# esp32_uart_co2_sensor.net
KiCad netlist of a schematic drawn in EAGLE
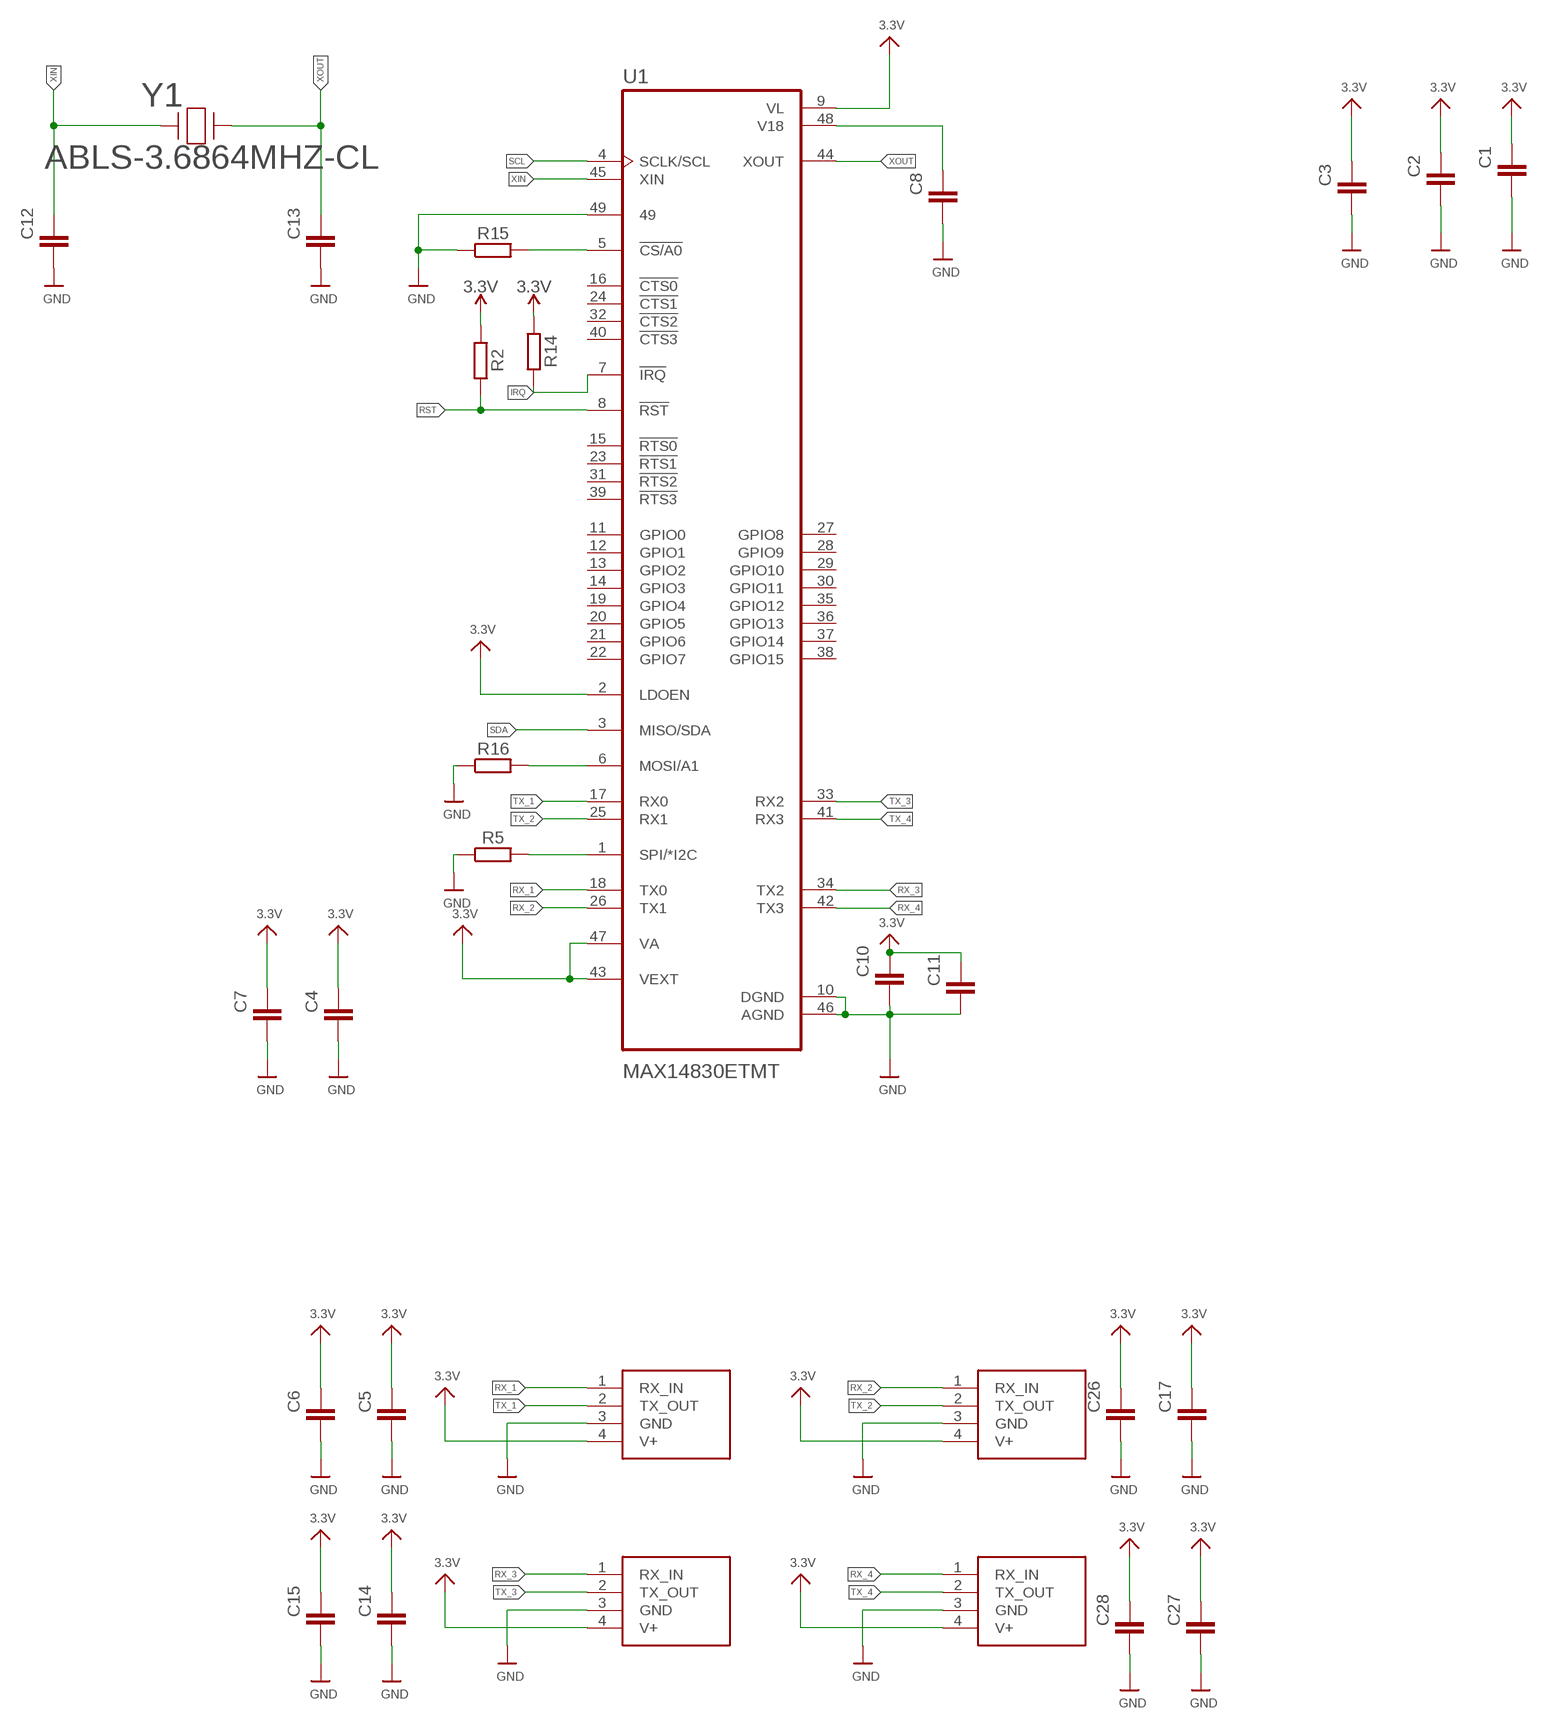
[diagram p0: schematic, sheet 1, part 1 of 2]
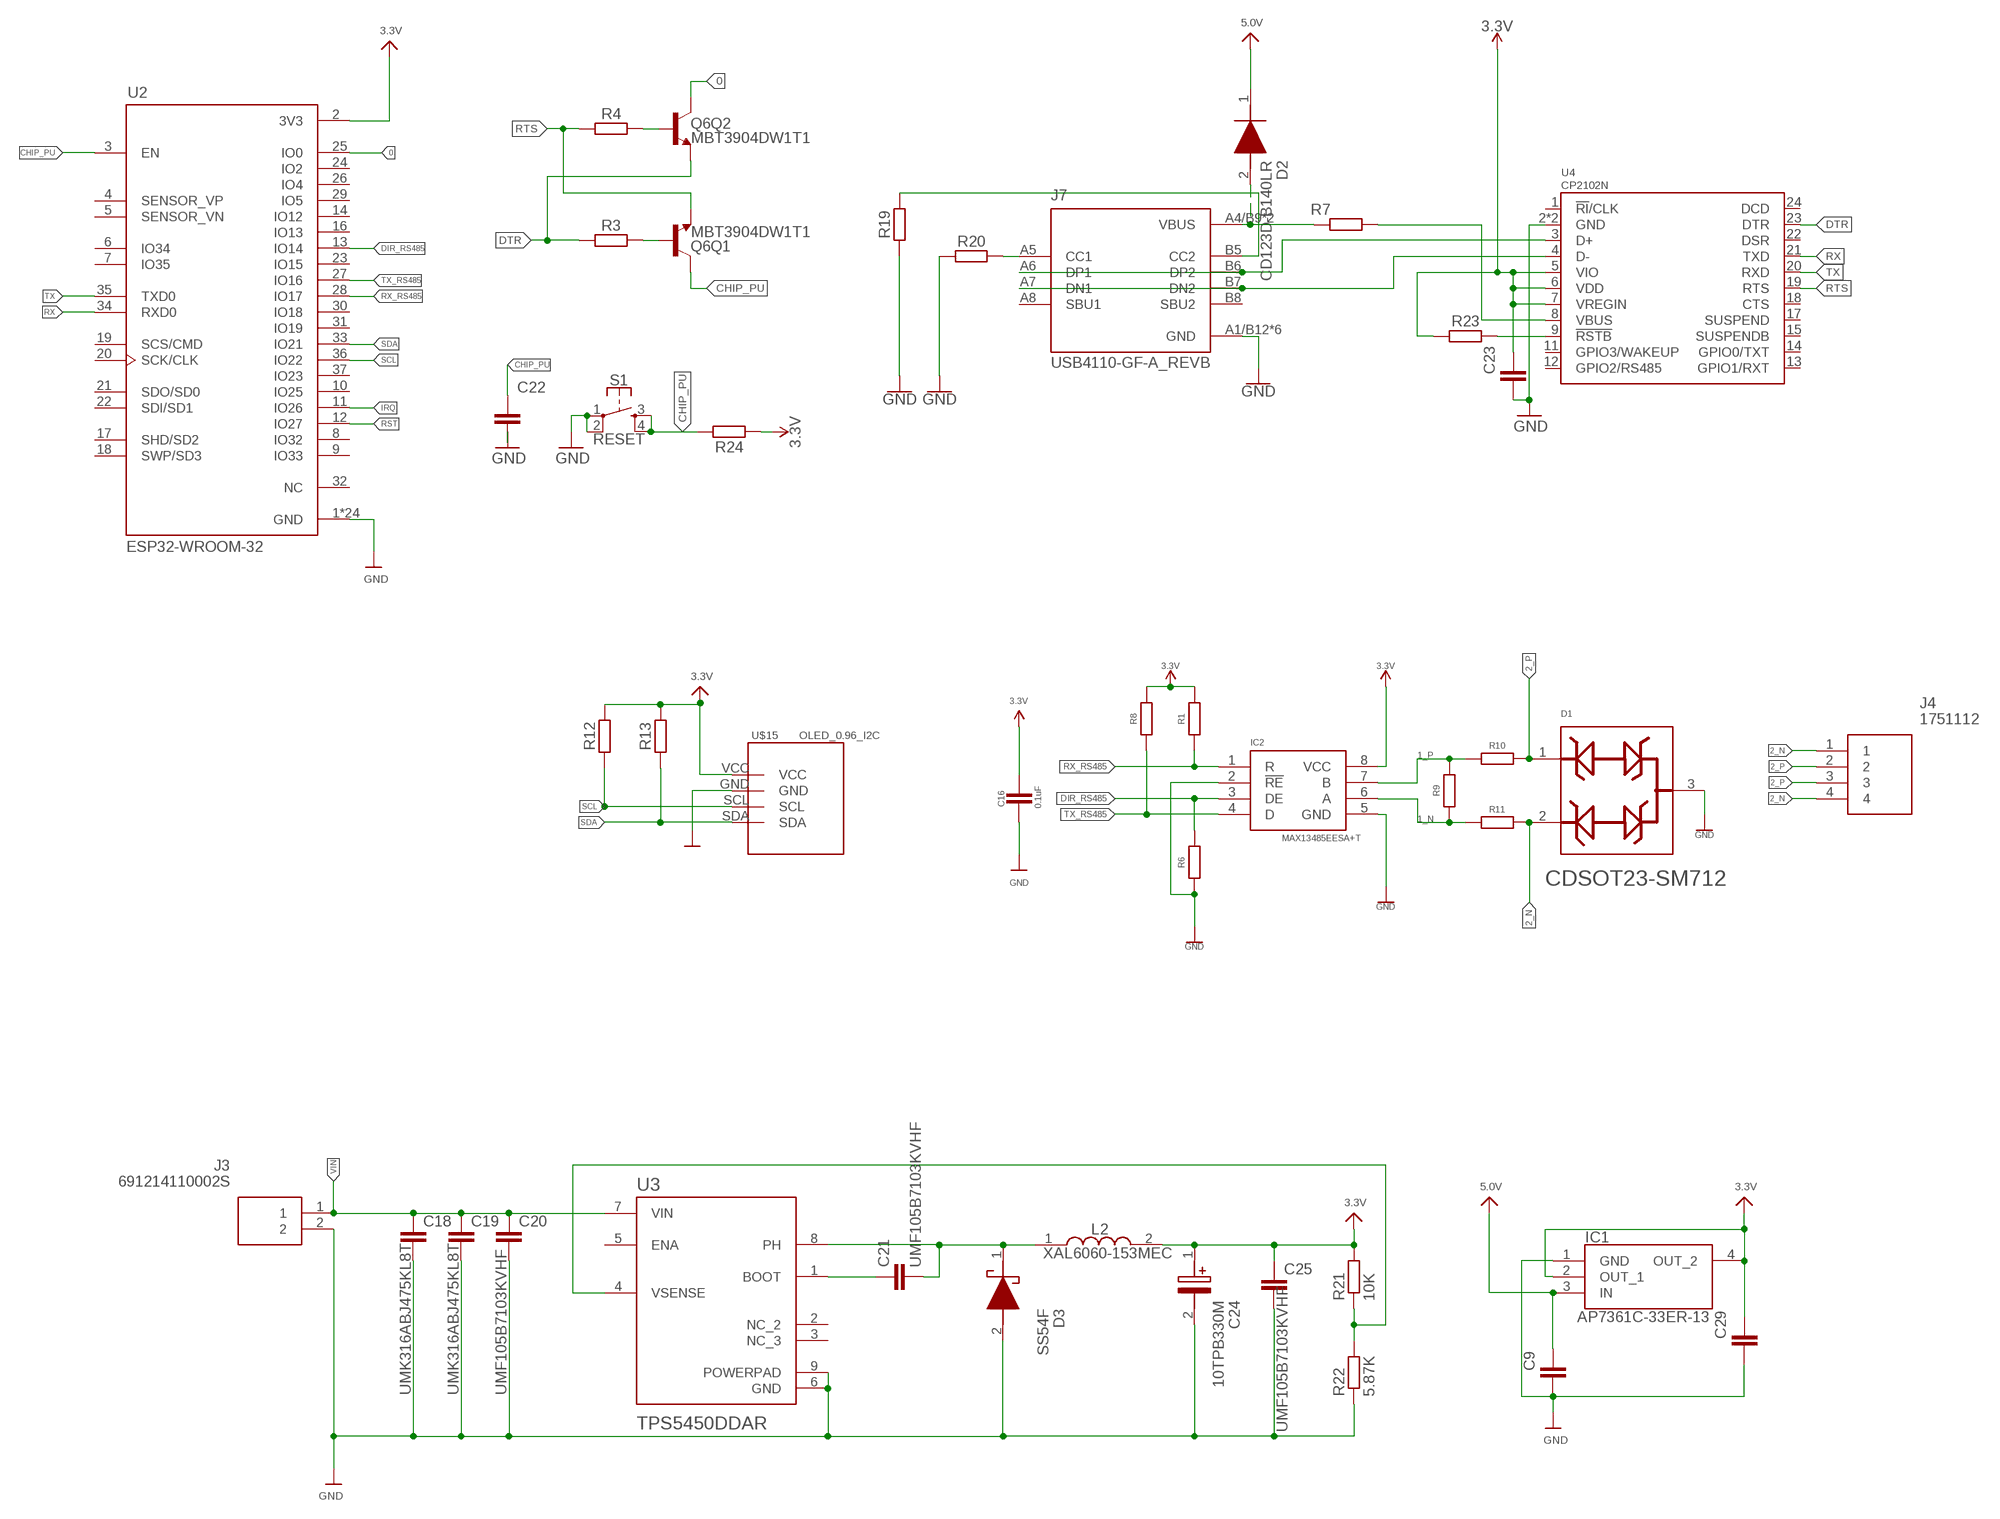
[diagram p1: schematic, sheet 1, part 2 of 2]

(export (version "E")
  (design (tool "Eeschema 10.0.6"))
  (components
    (comp (ref "C1")
      (value "10uF")
      (footprint "eagle-import:C0402")
      (libsource (lib "eagle-import") (part "C-EUC0402"))
    )
    (comp (ref "C2")
      (value "0.1uF")
      (footprint "eagle-import:C0402")
      (libsource (lib "eagle-import") (part "C-EUC0402"))
    )
    (comp (ref "C3")
      (value "1uF")
      (footprint "eagle-import:C0402")
      (libsource (lib "eagle-import") (part "C-EUC0402"))
    )
    (comp (ref "C4")
      (value "1uF")
      (footprint "eagle-import:C0402")
      (libsource (lib "eagle-import") (part "C-EUC0402"))
    )
    (comp (ref "C5")
      (value "1uF")
      (footprint "eagle-import:C0402")
      (libsource (lib "eagle-import") (part "C-EUC0402"))
    )
    (comp (ref "C6")
      (value "10uF")
      (footprint "eagle-import:C0402")
      (libsource (lib "eagle-import") (part "C-EUC0402"))
    )
    (comp (ref "C7")
      (value "10uF")
      (footprint "eagle-import:C0402")
      (libsource (lib "eagle-import") (part "C-EUC0402"))
    )
    (comp (ref "C8")
      (value "1uF")
      (footprint "eagle-import:C0402")
      (libsource (lib "eagle-import") (part "C-EUC0402"))
    )
    (comp (ref "C9")
      (value "4.7uF")
      (footprint "eagle-import:C0402")
      (libsource (lib "eagle-import") (part "C-EUC0402"))
    )
    (comp (ref "C10")
      (value "1uF")
      (footprint "eagle-import:C0402")
      (libsource (lib "eagle-import") (part "C-EUC0402"))
    )
    (comp (ref "C11")
      (value "1uF")
      (footprint "eagle-import:C0402")
      (libsource (lib "eagle-import") (part "C-EUC0402"))
    )
    (comp (ref "C12")
      (value "18pF")
      (footprint "eagle-import:C0402")
      (libsource (lib "eagle-import") (part "C-EUC0402"))
    )
    (comp (ref "C13")
      (value "18pF")
      (footprint "eagle-import:C0402")
      (libsource (lib "eagle-import") (part "C-EUC0402"))
    )
    (comp (ref "C14")
      (value "1uF")
      (footprint "eagle-import:C0402")
      (libsource (lib "eagle-import") (part "C-EUC0402"))
    )
    (comp (ref "C15")
      (value "10uF")
      (footprint "eagle-import:C0402")
      (libsource (lib "eagle-import") (part "C-EUC0402"))
    )
    (comp (ref "C16")
      (value "0.1uF")
      (footprint "eagle-import:0402-TIGHT")
      (libsource (lib "eagle-import") (part "0.1UF-0402T-16V-10%"))
    )
    (comp (ref "C17")
      (value "1uF")
      (footprint "eagle-import:C0402")
      (libsource (lib "eagle-import") (part "C-EUC0402"))
    )
    (comp (ref "C18")
      (value "UMK316ABJ475KL8T")
      (footprint "eagle-import:C1206")
      (libsource (lib "eagle-import") (part "C-EUC1206"))
    )
    (comp (ref "C19")
      (value "UMK316ABJ475KL8T")
      (footprint "eagle-import:C1206")
      (libsource (lib "eagle-import") (part "C-EUC1206"))
    )
    (comp (ref "C20")
      (value "UMF105B7103KVHF")
      (footprint "eagle-import:C0402")
      (libsource (lib "eagle-import") (part "C-EUC0402"))
    )
    (comp (ref "C21")
      (value "UMF105B7103KVHF")
      (footprint "eagle-import:C0402")
      (libsource (lib "eagle-import") (part "C-EUC0402"))
    )
    (comp (ref "C22")
      (value "1.0uF")
      (footprint "eagle-import:C0402")
      (libsource (lib "eagle-import") (part "C-EUC0402"))
    )
    (comp (ref "C23")
      (value "10uF")
      (footprint "eagle-import:C0402")
      (libsource (lib "eagle-import") (part "C-EUC0402"))
    )
    (comp (ref "C24")
      (value "10TPB330M")
      (footprint "eagle-import:CAPPM7343X400N")
      (fields (field (name "MOUSER_PART_NUMBER") "667-10TPB330M"))
      (libsource (lib "eagle-import") (part "10TPB330M"))
    )
    (comp (ref "C25")
      (value "UMF105B7103KVHF")
      (footprint "eagle-import:C0402")
      (libsource (lib "eagle-import") (part "C-EUC0402"))
    )
    (comp (ref "C26")
      (value "10uF")
      (footprint "eagle-import:C0402")
      (libsource (lib "eagle-import") (part "C-EUC0402"))
    )
    (comp (ref "C27")
      (value "1uF")
      (footprint "eagle-import:C0402")
      (libsource (lib "eagle-import") (part "C-EUC0402"))
    )
    (comp (ref "C28")
      (value "10uF")
      (footprint "eagle-import:C0402")
      (libsource (lib "eagle-import") (part "C-EUC0402"))
    )
    (comp (ref "C29")
      (value "4.7uF")
      (footprint "eagle-import:C0402")
      (libsource (lib "eagle-import") (part "C-EUC0402"))
    )
    (comp (ref "D1")
      (value "BOURNS_INC._CDSOT23-SM712BOURNS_INC._CDSOT23-SM712_0_0")
      (footprint "eagle-import:BOURNS_INC._CDSOT23-SM712_0")
      (fields
        (field (name "DIGIKEY_PART_NUMBER") "CDSOT23-SM712CT-ND")
        (field (name "MF") "Bourns Inc.")
        (field (name "MOUSER_PART_NUMBER") "652-CDSOT23-SM712")
      )
      (libsource (lib "eagle-import") (part "BOURNS_INC._CDSOT23-SM712BOURNS_INC._CDSOT23-SM712_0_0"))
    )
    (comp (ref "D2")
      (value "CD123D-B140LR")
      (footprint "eagle-import:CD123DB140LR")
      (fields (field (name "MOUSER_PART_NUMBER") "652-CD123D-B140LR"))
      (libsource (lib "eagle-import") (part "CD123D-B140LR"))
    )
    (comp (ref "D3")
      (value "SS54F")
      (footprint "eagle-import:SODFL4626X130N")
      (libsource (lib "eagle-import") (part "SS54F"))
    )
    (comp (ref "IC1")
      (value "AP7361C-33ER-13")
      (footprint "eagle-import:SOT230P700X180-4N")
      (fields (field (name "MOUSER_PART_NUMBER") "621-AP7361C-33ER-13"))
      (libsource (lib "eagle-import") (part "AP7361C-33ER-13"))
    )
    (comp (ref "IC2")
      (value "MAX13485EESA+T")
      (footprint "eagle-import:SOIC127P600X175-8N")
      (fields
        (field (name "ARROW_PART_NUMBER") "THVD1450DR")
        (field (name "MOUSER_PART_NUMBER") "595-THVD1450DR")
      )
      (libsource (lib "eagle-import") (part "THVD1450DR"))
    )
    (comp (ref "J3")
      (value "691214110002S")
      (footprint "eagle-import:691214110002S")
      (fields (field (name "MOUSER_PART_NUMBER") "710-691214110002S"))
      (libsource (lib "eagle-import") (part "691214110002S"))
    )
    (comp (ref "J4")
      (value "1751112")
      (footprint "eagle-import:1751112")
      (fields (field (name "MOUSER_PART_NUMBER") "651-1751112"))
      (libsource (lib "eagle-import") (part "1751112"))
    )
    (comp (ref "J7")
      (value "USB4110-GF-A_REVB")
      (footprint "eagle-import:GCT_USB4110-GF-A_REVB")
      (fields (field (name "MF") "GCT") (field (name "MP") "USB4110-GF-A"))
      (libsource (lib "eagle-import") (part "USB4110-GF-A_REVB"))
    )
    (comp (ref "L2")
      (value "XAL6060-153MEC")
      (footprint "eagle-import:XAL6060153MEC")
      (fields (field (name "MOUSER_PART_NUMBER") "994-XAL6060-153MEC"))
      (libsource (lib "eagle-import") (part "XAL6060-153MEC"))
    )
    (comp (ref "Q6")
      (value "MBT3904DW1T1")
      (footprint "eagle-import:SC70-6")
      (libsource (lib "eagle-import") (part "TRANS_NPN_DUAL-MBT3904DW1T1"))
    )
    (comp (ref "R1")
      (value "2.2k")
      (footprint "eagle-import:R0402")
      (libsource (lib "eagle-import") (part "R-EU_R0402"))
    )
    (comp (ref "R2")
      (value "10k")
      (footprint "eagle-import:R0402")
      (libsource (lib "eagle-import") (part "R-EU_R0402"))
    )
    (comp (ref "R3")
      (value "10k")
      (footprint "eagle-import:R0402")
      (libsource (lib "eagle-import") (part "R-EU_R0402"))
    )
    (comp (ref "R4")
      (value "10k")
      (footprint "eagle-import:R0402")
      (libsource (lib "eagle-import") (part "R-EU_R0402"))
    )
    (comp (ref "R5")
      (value "10k")
      (footprint "eagle-import:R0402")
      (libsource (lib "eagle-import") (part "R-EU_R0402"))
    )
    (comp (ref "R6")
      (value "2.2k")
      (footprint "eagle-import:R0603")
      (libsource (lib "eagle-import") (part "R-EU_R0603"))
    )
    (comp (ref "R7")
      (value "10")
      (footprint "eagle-import:R0603")
      (libsource (lib "eagle-import") (part "R-EU_R0603"))
    )
    (comp (ref "R8")
      (value "2.2k")
      (footprint "eagle-import:R0402")
      (libsource (lib "eagle-import") (part "R-EU_R0402"))
    )
    (comp (ref "R9")
      (value "120R")
      (footprint "eagle-import:R0603")
      (libsource (lib "eagle-import") (part "R-EU_R0603"))
    )
    (comp (ref "R10")
      (value "10Ω")
      (footprint "eagle-import:R0402")
      (libsource (lib "eagle-import") (part "R-EU_R0402"))
    )
    (comp (ref "R11")
      (value "10Ω")
      (footprint "eagle-import:R0402")
      (libsource (lib "eagle-import") (part "R-EU_R0402"))
    )
    (comp (ref "R12")
      (value "10k")
      (footprint "eagle-import:R0402")
      (libsource (lib "eagle-import") (part "R-EU_R0402"))
    )
    (comp (ref "R13")
      (value "10k")
      (footprint "eagle-import:R0402")
      (libsource (lib "eagle-import") (part "R-EU_R0402"))
    )
    (comp (ref "R14")
      (value "10k")
      (footprint "eagle-import:R0402")
      (libsource (lib "eagle-import") (part "R-EU_R0402"))
    )
    (comp (ref "R15")
      (value "10k")
      (footprint "eagle-import:R0402")
      (libsource (lib "eagle-import") (part "R-EU_R0402"))
    )
    (comp (ref "R16")
      (value "10k")
      (footprint "eagle-import:R0402")
      (libsource (lib "eagle-import") (part "R-EU_R0402"))
    )
    (comp (ref "R19")
      (value "5.1k")
      (footprint "eagle-import:R0402")
      (libsource (lib "eagle-import") (part "R-EU_R0402"))
    )
    (comp (ref "R20")
      (value "5.1k")
      (footprint "eagle-import:R0402")
      (libsource (lib "eagle-import") (part "R-EU_R0402"))
    )
    (comp (ref "R21")
      (value "10K")
      (footprint "eagle-import:R0402")
      (libsource (lib "eagle-import") (part "R-EU_R0402"))
    )
    (comp (ref "R22")
      (value "5.87K")
      (footprint "eagle-import:R0402")
      (libsource (lib "eagle-import") (part "R-EU_R0402"))
    )
    (comp (ref "R23")
      (value "1k")
      (footprint "eagle-import:R0402")
      (libsource (lib "eagle-import") (part "R-EU_R0402"))
    )
    (comp (ref "R24")
      (value "10k")
      (footprint "eagle-import:R0402")
      (libsource (lib "eagle-import") (part "R-EU_R0402"))
    )
    (comp (ref "S1")
      (value "RESET")
      (footprint "eagle-import:TACTILE_SWITCH_SMD_4.6X2.8MM")
      (libsource (lib "eagle-import") (part "MOMENTARY-SWITCH-SPST-2-SMD-4.6X2.8MM"))
    )
    (comp (ref "SEN1")
      (value "SPRINTIR-6S-20")
      (footprint "eagle-import:SPRINTIR-6S-20")
      (libsource (lib "eagle-import") (part "SPRINTIR-6S-20"))
    )
    (comp (ref "SEN2")
      (value "SPRINTIR-6S-20")
      (footprint "eagle-import:SPRINTIR-6S-20")
      (libsource (lib "eagle-import") (part "SPRINTIR-6S-20"))
    )
    (comp (ref "SEN3")
      (value "SPRINTIR-6S-20")
      (footprint "eagle-import:SPRINTIR-6S-20")
      (libsource (lib "eagle-import") (part "SPRINTIR-6S-20"))
    )
    (comp (ref "SEN4")
      (value "SPRINTIR-6S-20")
      (footprint "eagle-import:SPRINTIR-6S-20")
      (libsource (lib "eagle-import") (part "SPRINTIR-6S-20"))
    )
    (comp (ref "U$15")
      (value "OLED_0.96_I2C")
      (footprint "eagle-import:OLED_0.96_I2C")
      (libsource (lib "eagle-import") (part "OLED_0.96_I2C"))
    )
    (comp (ref "U1")
      (value "MAX14830ETMT")
      (footprint "eagle-import:QFN50P700X700X80-49N")
      (fields (field (name "MF") "Maxim Integrated") (field (name "MP") "MAX14830ETM+"))
      (libsource (lib "eagle-import") (part "MAX14830ETMT"))
    )
    (comp (ref "U2")
      (value "ESP32-WROOM-32")
      (footprint "eagle-import:MODULE_ESP32-WROOM-32")
      (fields (field (name "MF") "Espressif Systems"))
      (libsource (lib "eagle-import") (part "ESP32-WROOM-32"))
    )
    (comp (ref "U3")
      (value "TPS5450DDAR")
      (footprint "eagle-import:CONV_TPS5450DDAR")
      (fields (field (name "MF") "Texas Instruments"))
      (libsource (lib "eagle-import") (part "TPS5450DDAR"))
    )
    (comp (ref "U4")
      (value "CP2102N")
      (footprint "eagle-import:QFN24")
      (libsource (lib "eagle-import") (part "CP2102N"))
    )
    (comp (ref "Y1")
      (value "ABLS-3.6864MHZ-CL")
      (footprint "eagle-import:ABLS_SERIES_ABR")
      (fields
        (field (name "MANUFACTURER_PART_NUMBER") "ABLS-3.6864MHZ-CL-RESR-A-1-G-F")
        (field (name "COPYRIGHT") "Copyright (C) 2022 Ultra Librarian. All rights reserved.")
      )
      (libsource (lib "eagle-import") (part "ABLS-3.6864MHZ-CL-RESR-A-1-G-FABLS_SERIES_ABR"))
    )
  )
  (nets
    (net (code "1") (name "/1_N") (class "Default")
      (node (ref "IC2") (pin "6") (pinfunction "A_6") (pintype "bidirectional"))
      (node (ref "R11") (pin "1") (pinfunction "1_1") (pintype "passive"))
      (node (ref "R9") (pin "1") (pinfunction "1_1") (pintype "passive"))
    )
    (net (code "2") (name "/1_P") (class "Default")
      (node (ref "IC2") (pin "7") (pinfunction "B_7") (pintype "bidirectional"))
      (node (ref "R10") (pin "1") (pinfunction "1_1") (pintype "passive"))
      (node (ref "R9") (pin "2") (pinfunction "2_2") (pintype "passive"))
    )
    (net (code "3") (name "0") (class "Default")
      (node (ref "Q6") (pin "6") (pinfunction "C_6") (pintype "passive"))
      (node (ref "U2") (pin "25") (pinfunction "IO0_25") (pintype "bidirectional"))
    )
    (net (code "4") (name "2_N") (class "Default")
      (node (ref "D1") (pin "2") (pinfunction "2_2") (pintype "passive"))
      (node (ref "J4") (pin "1") (pinfunction "1_1") (pintype "bidirectional"))
      (node (ref "J4") (pin "4") (pinfunction "4_4") (pintype "bidirectional"))
      (node (ref "R11") (pin "2") (pinfunction "2_2") (pintype "passive"))
    )
    (net (code "5") (name "2_P") (class "Default")
      (node (ref "D1") (pin "1") (pinfunction "1_1") (pintype "passive"))
      (node (ref "J4") (pin "2") (pinfunction "2_2") (pintype "bidirectional"))
      (node (ref "J4") (pin "3") (pinfunction "3_3") (pintype "bidirectional"))
      (node (ref "R10") (pin "2") (pinfunction "2_2") (pintype "passive"))
    )
    (net (code "6") (name "3.3V") (class "Default")
      (node (ref "C1") (pin "1") (pinfunction "1_1") (pintype "passive"))
      (node (ref "C10") (pin "1") (pinfunction "1_1") (pintype "passive"))
      (node (ref "C11") (pin "1") (pinfunction "1_1") (pintype "passive"))
      (node (ref "C14") (pin "1") (pinfunction "1_1") (pintype "passive"))
      (node (ref "C15") (pin "1") (pinfunction "1_1") (pintype "passive"))
      (node (ref "C16") (pin "1") (pinfunction "1_1") (pintype "passive"))
      (node (ref "C17") (pin "1") (pinfunction "1_1") (pintype "passive"))
      (node (ref "C2") (pin "1") (pinfunction "1_1") (pintype "passive"))
      (node (ref "C23") (pin "1") (pinfunction "1_1") (pintype "passive"))
      (node (ref "C24") (pin "1") (pinfunction "+_1") (pintype "bidirectional"))
      (node (ref "C25") (pin "1") (pinfunction "1_1") (pintype "passive"))
      (node (ref "C26") (pin "1") (pinfunction "1_1") (pintype "passive"))
      (node (ref "C27") (pin "1") (pinfunction "1_1") (pintype "passive"))
      (node (ref "C28") (pin "1") (pinfunction "1_1") (pintype "passive"))
      (node (ref "C29") (pin "1") (pinfunction "1_1") (pintype "passive"))
      (node (ref "C3") (pin "1") (pinfunction "1_1") (pintype "passive"))
      (node (ref "C4") (pin "1") (pinfunction "1_1") (pintype "passive"))
      (node (ref "C5") (pin "1") (pinfunction "1_1") (pintype "passive"))
      (node (ref "C6") (pin "1") (pinfunction "1_1") (pintype "passive"))
      (node (ref "C7") (pin "1") (pinfunction "1_1") (pintype "passive"))
      (node (ref "IC1") (pin "2") (pinfunction "OUT_1_2") (pintype "bidirectional"))
      (node (ref "IC1") (pin "4") (pinfunction "OUT_2_4") (pintype "bidirectional"))
      (node (ref "IC2") (pin "8") (pinfunction "VCC_8") (pintype "bidirectional"))
      (node (ref "L2") (pin "2") (pinfunction "2_2") (pintype "bidirectional"))
      (node (ref "R1") (pin "2") (pinfunction "2_2") (pintype "passive"))
      (node (ref "R12") (pin "2") (pinfunction "2_2") (pintype "passive"))
      (node (ref "R13") (pin "2") (pinfunction "2_2") (pintype "passive"))
      (node (ref "R14") (pin "1") (pinfunction "1_1") (pintype "passive"))
      (node (ref "R2") (pin "1") (pinfunction "1_1") (pintype "passive"))
      (node (ref "R21") (pin "2") (pinfunction "2_2") (pintype "passive"))
      (node (ref "R23") (pin "1") (pinfunction "1_1") (pintype "passive"))
      (node (ref "R24") (pin "1") (pinfunction "1_1") (pintype "passive"))
      (node (ref "R8") (pin "2") (pinfunction "2_2") (pintype "passive"))
      (node (ref "SEN1") (pin "4") (pinfunction "V+_4") (pintype "bidirectional"))
      (node (ref "SEN2") (pin "4") (pinfunction "V+_4") (pintype "bidirectional"))
      (node (ref "SEN3") (pin "4") (pinfunction "V+_4") (pintype "bidirectional"))
      (node (ref "SEN4") (pin "4") (pinfunction "V+_4") (pintype "bidirectional"))
      (node (ref "U$15") (pin "VCC") (pinfunction "VCC_VCC") (pintype "bidirectional"))
      (node (ref "U1") (pin "2") (pinfunction "LDOEN_2") (pintype "bidirectional"))
      (node (ref "U1") (pin "43") (pinfunction "VEXT_43") (pintype "bidirectional"))
      (node (ref "U1") (pin "47") (pinfunction "VA_47") (pintype "bidirectional"))
      (node (ref "U1") (pin "9") (pinfunction "VL_9") (pintype "power_in"))
      (node (ref "U2") (pin "2") (pinfunction "3V3_2") (pintype "power_in"))
      (node (ref "U4") (pin "5") (pinfunction "VIO_5") (pintype "bidirectional"))
      (node (ref "U4") (pin "6") (pinfunction "VDD_6") (pintype "bidirectional"))
      (node (ref "U4") (pin "7") (pinfunction "VREGIN_7") (pintype "bidirectional"))
    )
    (net (code "7") (name "5.0V") (class "Default")
      (node (ref "C9") (pin "1") (pinfunction "1_1") (pintype "passive"))
      (node (ref "D2") (pin "1") (pinfunction "K_1") (pintype "bidirectional"))
      (node (ref "IC1") (pin "3") (pinfunction "IN_3") (pintype "bidirectional"))
    )
    (net (code "8") (name "CHIP_PU") (class "Default")
      (node (ref "C22") (pin "1") (pinfunction "1_1") (pintype "passive"))
      (node (ref "Q6") (pin "3") (pinfunction "C_3") (pintype "passive"))
      (node (ref "R24") (pin "2") (pinfunction "2_2") (pintype "passive"))
      (node (ref "S1") (pin "3") (pinfunction "3_3") (pintype "passive"))
      (node (ref "S1") (pin "4") (pinfunction "4_4") (pintype "passive"))
      (node (ref "U2") (pin "3") (pinfunction "EN_3") (pintype "input"))
    )
    (net (code "9") (name "DIR_RS485") (class "Default")
      (node (ref "IC2") (pin "3") (pinfunction "DE_3") (pintype "bidirectional"))
      (node (ref "R6") (pin "2") (pinfunction "2_2") (pintype "passive"))
      (node (ref "U2") (pin "13") (pinfunction "IO14_13") (pintype "bidirectional"))
    )
    (net (code "10") (name "DTR") (class "Default")
      (node (ref "Q6") (pin "1") (pinfunction "E_1") (pintype "passive"))
      (node (ref "R3") (pin "1") (pinfunction "1_1") (pintype "passive"))
      (node (ref "U4") (pin "23") (pinfunction "DTR_23") (pintype "bidirectional"))
    )
    (net (code "11") (name "GND") (class "Default")
      (node (ref "C1") (pin "2") (pinfunction "2_2") (pintype "passive"))
      (node (ref "C10") (pin "2") (pinfunction "2_2") (pintype "passive"))
      (node (ref "C11") (pin "2") (pinfunction "2_2") (pintype "passive"))
      (node (ref "C12") (pin "2") (pinfunction "2_2") (pintype "passive"))
      (node (ref "C13") (pin "2") (pinfunction "2_2") (pintype "passive"))
      (node (ref "C14") (pin "2") (pinfunction "2_2") (pintype "passive"))
      (node (ref "C15") (pin "2") (pinfunction "2_2") (pintype "passive"))
      (node (ref "C16") (pin "2") (pinfunction "2_2") (pintype "passive"))
      (node (ref "C17") (pin "2") (pinfunction "2_2") (pintype "passive"))
      (node (ref "C18") (pin "2") (pinfunction "2_2") (pintype "passive"))
      (node (ref "C19") (pin "2") (pinfunction "2_2") (pintype "passive"))
      (node (ref "C2") (pin "2") (pinfunction "2_2") (pintype "passive"))
      (node (ref "C20") (pin "2") (pinfunction "2_2") (pintype "passive"))
      (node (ref "C22") (pin "2") (pinfunction "2_2") (pintype "passive"))
      (node (ref "C23") (pin "2") (pinfunction "2_2") (pintype "passive"))
      (node (ref "C24") (pin "2") (pinfunction "-_2") (pintype "bidirectional"))
      (node (ref "C25") (pin "2") (pinfunction "2_2") (pintype "passive"))
      (node (ref "C26") (pin "2") (pinfunction "2_2") (pintype "passive"))
      (node (ref "C27") (pin "2") (pinfunction "2_2") (pintype "passive"))
      (node (ref "C28") (pin "2") (pinfunction "2_2") (pintype "passive"))
      (node (ref "C29") (pin "2") (pinfunction "2_2") (pintype "passive"))
      (node (ref "C3") (pin "2") (pinfunction "2_2") (pintype "passive"))
      (node (ref "C4") (pin "2") (pinfunction "2_2") (pintype "passive"))
      (node (ref "C5") (pin "2") (pinfunction "2_2") (pintype "passive"))
      (node (ref "C6") (pin "2") (pinfunction "2_2") (pintype "passive"))
      (node (ref "C7") (pin "2") (pinfunction "2_2") (pintype "passive"))
      (node (ref "C8") (pin "2") (pinfunction "2_2") (pintype "passive"))
      (node (ref "C9") (pin "2") (pinfunction "2_2") (pintype "passive"))
      (node (ref "D1") (pin "3") (pinfunction "3_3") (pintype "passive"))
      (node (ref "D3") (pin "2") (pinfunction "A_2") (pintype "bidirectional"))
      (node (ref "IC1") (pin "1") (pinfunction "GND_1") (pintype "bidirectional"))
      (node (ref "IC2") (pin "2") (pinfunction "~{RE}_2") (pintype "bidirectional"))
      (node (ref "IC2") (pin "5") (pinfunction "GND_5") (pintype "bidirectional"))
      (node (ref "J3") (pin "2") (pinfunction "2_2") (pintype "bidirectional"))
      (node (ref "J7") (pin "A1/B12") (pinfunction "GND_A1/B12") (pintype "power_in"))
      (node (ref "J7") (pin "B1/A12") (pinfunction "GND_B1/A12") (pintype "power_in"))
      (node (ref "J7") (pin "S1") (pinfunction "GND_S1") (pintype "power_in"))
      (node (ref "J7") (pin "S2") (pinfunction "GND_S2") (pintype "power_in"))
      (node (ref "J7") (pin "S3") (pinfunction "GND_S3") (pintype "power_in"))
      (node (ref "J7") (pin "S4") (pinfunction "GND_S4") (pintype "power_in"))
      (node (ref "R15") (pin "1") (pinfunction "1_1") (pintype "passive"))
      (node (ref "R16") (pin "1") (pinfunction "1_1") (pintype "passive"))
      (node (ref "R19") (pin "1") (pinfunction "1_1") (pintype "passive"))
      (node (ref "R20") (pin "1") (pinfunction "1_1") (pintype "passive"))
      (node (ref "R22") (pin "1") (pinfunction "1_1") (pintype "passive"))
      (node (ref "R5") (pin "1") (pinfunction "1_1") (pintype "passive"))
      (node (ref "R6") (pin "1") (pinfunction "1_1") (pintype "passive"))
      (node (ref "S1") (pin "1") (pinfunction "1_1") (pintype "passive"))
      (node (ref "S1") (pin "2") (pinfunction "2_2") (pintype "passive"))
      (node (ref "SEN1") (pin "3") (pinfunction "GND_3") (pintype "bidirectional"))
      (node (ref "SEN2") (pin "3") (pinfunction "GND_3") (pintype "bidirectional"))
      (node (ref "SEN3") (pin "3") (pinfunction "GND_3") (pintype "bidirectional"))
      (node (ref "SEN4") (pin "3") (pinfunction "GND_3") (pintype "bidirectional"))
      (node (ref "U$15") (pin "GND") (pinfunction "GND_GND") (pintype "bidirectional"))
      (node (ref "U1") (pin "10") (pinfunction "DGND_10") (pintype "power_in"))
      (node (ref "U1") (pin "46") (pinfunction "AGND_46") (pintype "power_in"))
      (node (ref "U1") (pin "49") (pinfunction "49_49") (pintype "bidirectional"))
      (node (ref "U2") (pin "1") (pinfunction "GND_1") (pintype "power_in"))
      (node (ref "U2") (pin "15") (pinfunction "GND_15") (pintype "power_in"))
      (node (ref "U2") (pin "38") (pinfunction "GND_38") (pintype "power_in"))
      (node (ref "U2") (pin "39_1") (pinfunction "GND_39_1") (pintype "power_in"))
      (node (ref "U2") (pin "39_10") (pinfunction "GND_39_10") (pintype "power_in"))
      (node (ref "U2") (pin "39_11") (pinfunction "GND_39_11") (pintype "power_in"))
      (node (ref "U2") (pin "39_12") (pinfunction "GND_39_12") (pintype "power_in"))
      (node (ref "U2") (pin "39_13") (pinfunction "GND_39_13") (pintype "power_in"))
      (node (ref "U2") (pin "39_14") (pinfunction "GND_39_14") (pintype "power_in"))
      (node (ref "U2") (pin "39_15") (pinfunction "GND_39_15") (pintype "power_in"))
      (node (ref "U2") (pin "39_16") (pinfunction "GND_39_16") (pintype "power_in"))
      (node (ref "U2") (pin "39_17") (pinfunction "GND_39_17") (pintype "power_in"))
      (node (ref "U2") (pin "39_18") (pinfunction "GND_39_18") (pintype "power_in"))
      (node (ref "U2") (pin "39_19") (pinfunction "GND_39_19") (pintype "power_in"))
      (node (ref "U2") (pin "39_2") (pinfunction "GND_39_2") (pintype "power_in"))
      (node (ref "U2") (pin "39_20") (pinfunction "GND_39_20") (pintype "power_in"))
      (node (ref "U2") (pin "39_21") (pinfunction "GND_39_21") (pintype "power_in"))
      (node (ref "U2") (pin "39_3") (pinfunction "GND_39_3") (pintype "power_in"))
      (node (ref "U2") (pin "39_4") (pinfunction "GND_39_4") (pintype "power_in"))
      (node (ref "U2") (pin "39_5") (pinfunction "GND_39_5") (pintype "power_in"))
      (node (ref "U2") (pin "39_6") (pinfunction "GND_39_6") (pintype "power_in"))
      (node (ref "U2") (pin "39_7") (pinfunction "GND_39_7") (pintype "power_in"))
      (node (ref "U2") (pin "39_8") (pinfunction "GND_39_8") (pintype "power_in"))
      (node (ref "U2") (pin "39_9") (pinfunction "GND_39_9") (pintype "power_in"))
      (node (ref "U3") (pin "6") (pinfunction "GND_6") (pintype "power_in"))
      (node (ref "U3") (pin "9") (pinfunction "POWERPAD_9") (pintype "power_in"))
      (node (ref "U4") (pin "2") (pinfunction "GND_2") (pintype "bidirectional"))
      (node (ref "U4") (pin "PAD") (pinfunction "GND_PAD") (pintype "bidirectional"))
    )
    (net (code "12") (name "IRQ") (class "Default")
      (node (ref "R14") (pin "2") (pinfunction "2_2") (pintype "passive"))
      (node (ref "U1") (pin "7") (pinfunction "~{IRQ}_7") (pintype "bidirectional"))
      (node (ref "U2") (pin "11") (pinfunction "IO26_11") (pintype "bidirectional"))
    )
    (net (code "13") (name "Net-(D2-A)") (class "Default")
      (node (ref "D2") (pin "2") (pinfunction "A_2") (pintype "bidirectional"))
      (node (ref "J7") (pin "A4/B9") (pinfunction "VBUS_A4/B9") (pintype "power_in"))
      (node (ref "J7") (pin "B4/A9") (pinfunction "VBUS_B4/A9") (pintype "power_in"))
      (node (ref "R7") (pin "1") (pinfunction "1_1") (pintype "passive"))
    )
    (net (code "14") (name "Net-(D3-K)") (class "Default")
      (node (ref "C21") (pin "2") (pinfunction "2_2") (pintype "passive"))
      (node (ref "D3") (pin "1") (pinfunction "K_1") (pintype "bidirectional"))
      (node (ref "L2") (pin "1") (pinfunction "1_1") (pintype "bidirectional"))
      (node (ref "U3") (pin "8") (pinfunction "PH_8") (pintype "output"))
    )
    (net (code "15") (name "Net-(J7-CC1)") (class "Default")
      (node (ref "J7") (pin "A5") (pinfunction "CC1_A5") (pintype "bidirectional"))
      (node (ref "R20") (pin "2") (pinfunction "2_2") (pintype "passive"))
    )
    (net (code "16") (name "Net-(J7-CC2)") (class "Default")
      (node (ref "J7") (pin "B5") (pinfunction "CC2_B5") (pintype "bidirectional"))
      (node (ref "R19") (pin "2") (pinfunction "2_2") (pintype "passive"))
    )
    (net (code "17") (name "Net-(J7-DN1)") (class "Default")
      (node (ref "J7") (pin "A7") (pinfunction "DN1_A7") (pintype "bidirectional"))
      (node (ref "J7") (pin "B7") (pinfunction "DN2_B7") (pintype "bidirectional"))
      (node (ref "U4") (pin "4") (pinfunction "D-_4") (pintype "bidirectional"))
    )
    (net (code "18") (name "Net-(J7-DP1)") (class "Default")
      (node (ref "J7") (pin "A6") (pinfunction "DP1_A6") (pintype "bidirectional"))
      (node (ref "J7") (pin "B6") (pinfunction "DP2_B6") (pintype "bidirectional"))
      (node (ref "U4") (pin "3") (pinfunction "D+_3") (pintype "bidirectional"))
    )
    (net (code "19") (name "Net-(Q6A-B)") (class "Default")
      (node (ref "Q6") (pin "5") (pinfunction "B_5") (pintype "passive"))
      (node (ref "R3") (pin "2") (pinfunction "2_2") (pintype "passive"))
    )
    (net (code "20") (name "Net-(Q6B-B)") (class "Default")
      (node (ref "Q6") (pin "2") (pinfunction "B_2") (pintype "passive"))
      (node (ref "R4") (pin "2") (pinfunction "2_2") (pintype "passive"))
    )
    (net (code "21") (name "Net-(U1-MOSI{slash}A1)") (class "Default")
      (node (ref "R16") (pin "2") (pinfunction "2_2") (pintype "passive"))
      (node (ref "U1") (pin "6") (pinfunction "MOSI/A1_6") (pintype "bidirectional"))
    )
    (net (code "22") (name "Net-(U1-SPI{slash}*I2C)") (class "Default")
      (node (ref "R5") (pin "2") (pinfunction "2_2") (pintype "passive"))
      (node (ref "U1") (pin "1") (pinfunction "SPI/*I2C_1") (pintype "bidirectional"))
    )
    (net (code "23") (name "Net-(U1-V18)") (class "Default")
      (node (ref "C8") (pin "1") (pinfunction "1_1") (pintype "passive"))
      (node (ref "U1") (pin "48") (pinfunction "V18_48") (pintype "power_in"))
    )
    (net (code "24") (name "Net-(U1-~{CS{slash}A0})") (class "Default")
      (node (ref "R15") (pin "2") (pinfunction "2_2") (pintype "passive"))
      (node (ref "U1") (pin "5") (pinfunction "~{CS/A0}_5") (pintype "bidirectional"))
    )
    (net (code "25") (name "Net-(U3-BOOT)") (class "Default")
      (node (ref "C21") (pin "1") (pinfunction "1_1") (pintype "passive"))
      (node (ref "U3") (pin "1") (pinfunction "BOOT_1") (pintype "output"))
    )
    (net (code "26") (name "Net-(U3-VSENSE)") (class "Default")
      (node (ref "R21") (pin "1") (pinfunction "1_1") (pintype "passive"))
      (node (ref "R22") (pin "2") (pinfunction "2_2") (pintype "passive"))
      (node (ref "U3") (pin "4") (pinfunction "VSENSE_4") (pintype "input"))
    )
    (net (code "27") (name "Net-(U4-VBUS)") (class "Default")
      (node (ref "R7") (pin "2") (pinfunction "2_2") (pintype "passive"))
      (node (ref "U4") (pin "8") (pinfunction "VBUS_8") (pintype "bidirectional"))
    )
    (net (code "28") (name "Net-(U4-~{RSTB})") (class "Default")
      (node (ref "R23") (pin "2") (pinfunction "2_2") (pintype "passive"))
      (node (ref "U4") (pin "9") (pinfunction "~{RSTB}_9") (pintype "bidirectional"))
    )
    (net (code "29") (name "RST") (class "Default")
      (node (ref "R2") (pin "2") (pinfunction "2_2") (pintype "passive"))
      (node (ref "U1") (pin "8") (pinfunction "~{RST}_8") (pintype "bidirectional"))
      (node (ref "U2") (pin "12") (pinfunction "IO27_12") (pintype "bidirectional"))
    )
    (net (code "30") (name "RTS") (class "Default")
      (node (ref "Q6") (pin "4") (pinfunction "E_4") (pintype "passive"))
      (node (ref "R4") (pin "1") (pinfunction "1_1") (pintype "passive"))
      (node (ref "U4") (pin "19") (pinfunction "RTS_19") (pintype "bidirectional"))
    )
    (net (code "31") (name "RX") (class "Default")
      (node (ref "U2") (pin "34") (pinfunction "RXD0_34") (pintype "bidirectional"))
      (node (ref "U4") (pin "21") (pinfunction "TXD_21") (pintype "bidirectional"))
    )
    (net (code "32") (name "RX_1") (class "Default")
      (node (ref "SEN1") (pin "1") (pinfunction "RX_IN_1") (pintype "bidirectional"))
      (node (ref "U1") (pin "18") (pinfunction "TX0_18") (pintype "bidirectional"))
    )
    (net (code "33") (name "RX_2") (class "Default")
      (node (ref "SEN2") (pin "1") (pinfunction "RX_IN_1") (pintype "bidirectional"))
      (node (ref "U1") (pin "26") (pinfunction "TX1_26") (pintype "bidirectional"))
    )
    (net (code "34") (name "RX_3") (class "Default")
      (node (ref "SEN3") (pin "1") (pinfunction "RX_IN_1") (pintype "bidirectional"))
      (node (ref "U1") (pin "34") (pinfunction "TX2_34") (pintype "bidirectional"))
    )
    (net (code "35") (name "RX_4") (class "Default")
      (node (ref "SEN4") (pin "1") (pinfunction "RX_IN_1") (pintype "bidirectional"))
      (node (ref "U1") (pin "42") (pinfunction "TX3_42") (pintype "bidirectional"))
    )
    (net (code "36") (name "RX_RS485") (class "Default")
      (node (ref "IC2") (pin "1") (pinfunction "R_1") (pintype "bidirectional"))
      (node (ref "R1") (pin "1") (pinfunction "1_1") (pintype "passive"))
      (node (ref "U2") (pin "28") (pinfunction "IO17_28") (pintype "bidirectional"))
    )
    (net (code "37") (name "SCL") (class "Default")
      (node (ref "R12") (pin "1") (pinfunction "1_1") (pintype "passive"))
      (node (ref "U$15") (pin "SCL") (pinfunction "SCL_SCL") (pintype "bidirectional"))
      (node (ref "U1") (pin "4") (pinfunction "SCLK/SCL_4") (pintype "input"))
      (node (ref "U2") (pin "36") (pinfunction "IO22_36") (pintype "bidirectional"))
    )
    (net (code "38") (name "SDA") (class "Default")
      (node (ref "R13") (pin "1") (pinfunction "1_1") (pintype "passive"))
      (node (ref "U$15") (pin "SDA") (pinfunction "SDA_SDA") (pintype "bidirectional"))
      (node (ref "U1") (pin "3") (pinfunction "MISO/SDA_3") (pintype "bidirectional"))
      (node (ref "U2") (pin "33") (pinfunction "IO21_33") (pintype "bidirectional"))
    )
    (net (code "39") (name "TX") (class "Default")
      (node (ref "U2") (pin "35") (pinfunction "TXD0_35") (pintype "bidirectional"))
      (node (ref "U4") (pin "20") (pinfunction "RXD_20") (pintype "bidirectional"))
    )
    (net (code "40") (name "TX_1") (class "Default")
      (node (ref "SEN1") (pin "2") (pinfunction "TX_OUT_2") (pintype "bidirectional"))
      (node (ref "U1") (pin "17") (pinfunction "RX0_17") (pintype "bidirectional"))
    )
    (net (code "41") (name "TX_2") (class "Default")
      (node (ref "SEN2") (pin "2") (pinfunction "TX_OUT_2") (pintype "bidirectional"))
      (node (ref "U1") (pin "25") (pinfunction "RX1_25") (pintype "bidirectional"))
    )
    (net (code "42") (name "TX_3") (class "Default")
      (node (ref "SEN3") (pin "2") (pinfunction "TX_OUT_2") (pintype "bidirectional"))
      (node (ref "U1") (pin "33") (pinfunction "RX2_33") (pintype "bidirectional"))
    )
    (net (code "43") (name "TX_4") (class "Default")
      (node (ref "SEN4") (pin "2") (pinfunction "TX_OUT_2") (pintype "bidirectional"))
      (node (ref "U1") (pin "41") (pinfunction "RX3_41") (pintype "bidirectional"))
    )
    (net (code "44") (name "TX_RS485") (class "Default")
      (node (ref "IC2") (pin "4") (pinfunction "D_4") (pintype "bidirectional"))
      (node (ref "R8") (pin "1") (pinfunction "1_1") (pintype "passive"))
      (node (ref "U2") (pin "27") (pinfunction "IO16_27") (pintype "bidirectional"))
    )
    (net (code "45") (name "VIN") (class "Default")
      (node (ref "C18") (pin "1") (pinfunction "1_1") (pintype "passive"))
      (node (ref "C19") (pin "1") (pinfunction "1_1") (pintype "passive"))
      (node (ref "C20") (pin "1") (pinfunction "1_1") (pintype "passive"))
      (node (ref "J3") (pin "1") (pinfunction "1_1") (pintype "bidirectional"))
      (node (ref "U3") (pin "7") (pinfunction "VIN_7") (pintype "power_in"))
    )
    (net (code "46") (name "XIN") (class "Default")
      (node (ref "C12") (pin "1") (pinfunction "1_1") (pintype "passive"))
      (node (ref "U1") (pin "45") (pinfunction "XIN_45") (pintype "input"))
      (node (ref "Y1") (pin "1") (pinfunction "1_1") (pintype "passive"))
    )
    (net (code "47") (name "XOUT") (class "Default")
      (node (ref "C13") (pin "1") (pinfunction "1_1") (pintype "passive"))
      (node (ref "U1") (pin "44") (pinfunction "XOUT_44") (pintype "output"))
      (node (ref "Y1") (pin "2") (pinfunction "2_2") (pintype "passive"))
    )
    (net (code "48") (name "unconnected-(J7-SBU1-PadA8)") (class "Default")
      (node (ref "J7") (pin "A8") (pinfunction "SBU1_A8") (pintype "bidirectional"))
    )
    (net (code "49") (name "unconnected-(J7-SBU2-PadB8)") (class "Default")
      (node (ref "J7") (pin "B8") (pinfunction "SBU2_B8") (pintype "bidirectional"))
    )
    (net (code "50") (name "unconnected-(U1-GPIO0-Pad11)") (class "Default")
      (node (ref "U1") (pin "11") (pinfunction "GPIO0_11") (pintype "bidirectional"))
    )
    (net (code "51") (name "unconnected-(U1-GPIO1-Pad12)") (class "Default")
      (node (ref "U1") (pin "12") (pinfunction "GPIO1_12") (pintype "bidirectional"))
    )
    (net (code "52") (name "unconnected-(U1-GPIO2-Pad13)") (class "Default")
      (node (ref "U1") (pin "13") (pinfunction "GPIO2_13") (pintype "bidirectional"))
    )
    (net (code "53") (name "unconnected-(U1-GPIO3-Pad14)") (class "Default")
      (node (ref "U1") (pin "14") (pinfunction "GPIO3_14") (pintype "bidirectional"))
    )
    (net (code "54") (name "unconnected-(U1-GPIO4-Pad19)") (class "Default")
      (node (ref "U1") (pin "19") (pinfunction "GPIO4_19") (pintype "bidirectional"))
    )
    (net (code "55") (name "unconnected-(U1-GPIO5-Pad20)") (class "Default")
      (node (ref "U1") (pin "20") (pinfunction "GPIO5_20") (pintype "bidirectional"))
    )
    (net (code "56") (name "unconnected-(U1-GPIO6-Pad21)") (class "Default")
      (node (ref "U1") (pin "21") (pinfunction "GPIO6_21") (pintype "bidirectional"))
    )
    (net (code "57") (name "unconnected-(U1-GPIO7-Pad22)") (class "Default")
      (node (ref "U1") (pin "22") (pinfunction "GPIO7_22") (pintype "bidirectional"))
    )
    (net (code "58") (name "unconnected-(U1-GPIO8-Pad27)") (class "Default")
      (node (ref "U1") (pin "27") (pinfunction "GPIO8_27") (pintype "bidirectional"))
    )
    (net (code "59") (name "unconnected-(U1-GPIO9-Pad28)") (class "Default")
      (node (ref "U1") (pin "28") (pinfunction "GPIO9_28") (pintype "bidirectional"))
    )
    (net (code "60") (name "unconnected-(U1-GPIO10-Pad29)") (class "Default")
      (node (ref "U1") (pin "29") (pinfunction "GPIO10_29") (pintype "bidirectional"))
    )
    (net (code "61") (name "unconnected-(U1-GPIO11-Pad30)") (class "Default")
      (node (ref "U1") (pin "30") (pinfunction "GPIO11_30") (pintype "bidirectional"))
    )
    (net (code "62") (name "unconnected-(U1-GPIO12-Pad35)") (class "Default")
      (node (ref "U1") (pin "35") (pinfunction "GPIO12_35") (pintype "bidirectional"))
    )
    (net (code "63") (name "unconnected-(U1-GPIO13-Pad36)") (class "Default")
      (node (ref "U1") (pin "36") (pinfunction "GPIO13_36") (pintype "bidirectional"))
    )
    (net (code "64") (name "unconnected-(U1-GPIO14-Pad37)") (class "Default")
      (node (ref "U1") (pin "37") (pinfunction "GPIO14_37") (pintype "bidirectional"))
    )
    (net (code "65") (name "unconnected-(U1-GPIO15-Pad38)") (class "Default")
      (node (ref "U1") (pin "38") (pinfunction "GPIO15_38") (pintype "bidirectional"))
    )
    (net (code "66") (name "unconnected-(U1-~{CTS0}-Pad16)") (class "Default")
      (node (ref "U1") (pin "16") (pinfunction "~{CTS0}_16") (pintype "bidirectional"))
    )
    (net (code "67") (name "unconnected-(U1-~{CTS1}-Pad24)") (class "Default")
      (node (ref "U1") (pin "24") (pinfunction "~{CTS1}_24") (pintype "bidirectional"))
    )
    (net (code "68") (name "unconnected-(U1-~{CTS2}-Pad32)") (class "Default")
      (node (ref "U1") (pin "32") (pinfunction "~{CTS2}_32") (pintype "bidirectional"))
    )
    (net (code "69") (name "unconnected-(U1-~{CTS3}-Pad40)") (class "Default")
      (node (ref "U1") (pin "40") (pinfunction "~{CTS3}_40") (pintype "bidirectional"))
    )
    (net (code "70") (name "unconnected-(U1-~{RTS0}-Pad15)") (class "Default")
      (node (ref "U1") (pin "15") (pinfunction "~{RTS0}_15") (pintype "bidirectional"))
    )
    (net (code "71") (name "unconnected-(U1-~{RTS1}-Pad23)") (class "Default")
      (node (ref "U1") (pin "23") (pinfunction "~{RTS1}_23") (pintype "bidirectional"))
    )
    (net (code "72") (name "unconnected-(U1-~{RTS2}-Pad31)") (class "Default")
      (node (ref "U1") (pin "31") (pinfunction "~{RTS2}_31") (pintype "bidirectional"))
    )
    (net (code "73") (name "unconnected-(U1-~{RTS3}-Pad39)") (class "Default")
      (node (ref "U1") (pin "39") (pinfunction "~{RTS3}_39") (pintype "bidirectional"))
    )
    (net (code "74") (name "unconnected-(U2-IO2-Pad24)") (class "Default")
      (node (ref "U2") (pin "24") (pinfunction "IO2_24") (pintype "bidirectional"))
    )
    (net (code "75") (name "unconnected-(U2-IO4-Pad26)") (class "Default")
      (node (ref "U2") (pin "26") (pinfunction "IO4_26") (pintype "bidirectional"))
    )
    (net (code "76") (name "unconnected-(U2-IO5-Pad29)") (class "Default")
      (node (ref "U2") (pin "29") (pinfunction "IO5_29") (pintype "bidirectional"))
    )
    (net (code "77") (name "unconnected-(U2-IO12-Pad14)") (class "Default")
      (node (ref "U2") (pin "14") (pinfunction "IO12_14") (pintype "bidirectional"))
    )
    (net (code "78") (name "unconnected-(U2-IO13-Pad16)") (class "Default")
      (node (ref "U2") (pin "16") (pinfunction "IO13_16") (pintype "bidirectional"))
    )
    (net (code "79") (name "unconnected-(U2-IO15-Pad23)") (class "Default")
      (node (ref "U2") (pin "23") (pinfunction "IO15_23") (pintype "bidirectional"))
    )
    (net (code "80") (name "unconnected-(U2-IO18-Pad30)") (class "Default")
      (node (ref "U2") (pin "30") (pinfunction "IO18_30") (pintype "bidirectional"))
    )
    (net (code "81") (name "unconnected-(U2-IO19-Pad31)") (class "Default")
      (node (ref "U2") (pin "31") (pinfunction "IO19_31") (pintype "bidirectional"))
    )
    (net (code "82") (name "unconnected-(U2-IO23-Pad37)") (class "Default")
      (node (ref "U2") (pin "37") (pinfunction "IO23_37") (pintype "bidirectional"))
    )
    (net (code "83") (name "unconnected-(U2-IO25-Pad10)") (class "Default")
      (node (ref "U2") (pin "10") (pinfunction "IO25_10") (pintype "bidirectional"))
    )
    (net (code "84") (name "unconnected-(U2-IO32-Pad8)") (class "Default")
      (node (ref "U2") (pin "8") (pinfunction "IO32_8") (pintype "bidirectional"))
    )
    (net (code "85") (name "unconnected-(U2-IO33-Pad9)") (class "Default")
      (node (ref "U2") (pin "9") (pinfunction "IO33_9") (pintype "bidirectional"))
    )
    (net (code "86") (name "unconnected-(U2-IO34-Pad6)") (class "Default")
      (node (ref "U2") (pin "6") (pinfunction "IO34_6") (pintype "input"))
    )
    (net (code "87") (name "unconnected-(U2-IO35-Pad7)") (class "Default")
      (node (ref "U2") (pin "7") (pinfunction "IO35_7") (pintype "input"))
    )
    (net (code "88") (name "unconnected-(U2-NC-Pad32)") (class "Default")
      (node (ref "U2") (pin "32") (pinfunction "NC_32") (pintype "no_connect"))
    )
    (net (code "89") (name "unconnected-(U2-SCK{slash}CLK-Pad20)") (class "Default")
      (node (ref "U2") (pin "20") (pinfunction "SCK/CLK_20") (pintype "bidirectional"))
    )
    (net (code "90") (name "unconnected-(U2-SCS{slash}CMD-Pad19)") (class "Default")
      (node (ref "U2") (pin "19") (pinfunction "SCS/CMD_19") (pintype "bidirectional"))
    )
    (net (code "91") (name "unconnected-(U2-SDI{slash}SD1-Pad22)") (class "Default")
      (node (ref "U2") (pin "22") (pinfunction "SDI/SD1_22") (pintype "bidirectional"))
    )
    (net (code "92") (name "unconnected-(U2-SDO{slash}SD0-Pad21)") (class "Default")
      (node (ref "U2") (pin "21") (pinfunction "SDO/SD0_21") (pintype "bidirectional"))
    )
    (net (code "93") (name "unconnected-(U2-SENSOR_VN-Pad5)") (class "Default")
      (node (ref "U2") (pin "5") (pinfunction "SENSOR_VN_5") (pintype "input"))
    )
    (net (code "94") (name "unconnected-(U2-SENSOR_VP-Pad4)") (class "Default")
      (node (ref "U2") (pin "4") (pinfunction "SENSOR_VP_4") (pintype "input"))
    )
    (net (code "95") (name "unconnected-(U2-SHD{slash}SD2-Pad17)") (class "Default")
      (node (ref "U2") (pin "17") (pinfunction "SHD/SD2_17") (pintype "bidirectional"))
    )
    (net (code "96") (name "unconnected-(U2-SWP{slash}SD3-Pad18)") (class "Default")
      (node (ref "U2") (pin "18") (pinfunction "SWP/SD3_18") (pintype "bidirectional"))
    )
    (net (code "97") (name "unconnected-(U3-ENA-Pad5)") (class "Default")
      (node (ref "U3") (pin "5") (pinfunction "ENA_5") (pintype "input"))
    )
    (net (code "98") (name "unconnected-(U3-NC_2-Pad2)") (class "Default")
      (node (ref "U3") (pin "2") (pinfunction "NC_2_2") (pintype "no_connect"))
    )
    (net (code "99") (name "unconnected-(U3-NC_3-Pad3)") (class "Default")
      (node (ref "U3") (pin "3") (pinfunction "NC_3_3") (pintype "no_connect"))
    )
    (net (code "100") (name "unconnected-(U4-CTS-Pad18)") (class "Default")
      (node (ref "U4") (pin "18") (pinfunction "CTS_18") (pintype "bidirectional"))
    )
    (net (code "101") (name "unconnected-(U4-DCD-Pad24)") (class "Default")
      (node (ref "U4") (pin "24") (pinfunction "DCD_24") (pintype "bidirectional"))
    )
    (net (code "102") (name "unconnected-(U4-DSR-Pad22)") (class "Default")
      (node (ref "U4") (pin "22") (pinfunction "DSR_22") (pintype "bidirectional"))
    )
    (net (code "103") (name "unconnected-(U4-GPIO0{slash}TXT-Pad14)") (class "Default")
      (node (ref "U4") (pin "14") (pinfunction "GPIO0/TXT_14") (pintype "bidirectional"))
    )
    (net (code "104") (name "unconnected-(U4-GPIO1{slash}RXT-Pad13)") (class "Default")
      (node (ref "U4") (pin "13") (pinfunction "GPIO1/RXT_13") (pintype "bidirectional"))
    )
    (net (code "105") (name "unconnected-(U4-GPIO2{slash}RS485-Pad12)") (class "Default")
      (node (ref "U4") (pin "12") (pinfunction "GPIO2/RS485_12") (pintype "bidirectional"))
    )
    (net (code "106") (name "unconnected-(U4-GPIO3{slash}WAKEUP-Pad11)") (class "Default")
      (node (ref "U4") (pin "11") (pinfunction "GPIO3/WAKEUP_11") (pintype "bidirectional"))
    )
    (net (code "107") (name "unconnected-(U4-SUSPEND-Pad17)") (class "Default")
      (node (ref "U4") (pin "17") (pinfunction "SUSPEND_17") (pintype "bidirectional"))
    )
    (net (code "108") (name "unconnected-(U4-SUSPENDB-Pad15)") (class "Default")
      (node (ref "U4") (pin "15") (pinfunction "SUSPENDB_15") (pintype "bidirectional"))
    )
    (net (code "109") (name "unconnected-(U4-~{RI}{slash}CLK-Pad1)") (class "Default")
      (node (ref "U4") (pin "1") (pinfunction "~{RI}/CLK_1") (pintype "bidirectional"))
    )
  )
)
